# CarGeoLogger.net
KiCad netlist of a schematic drawn in Altium Designer
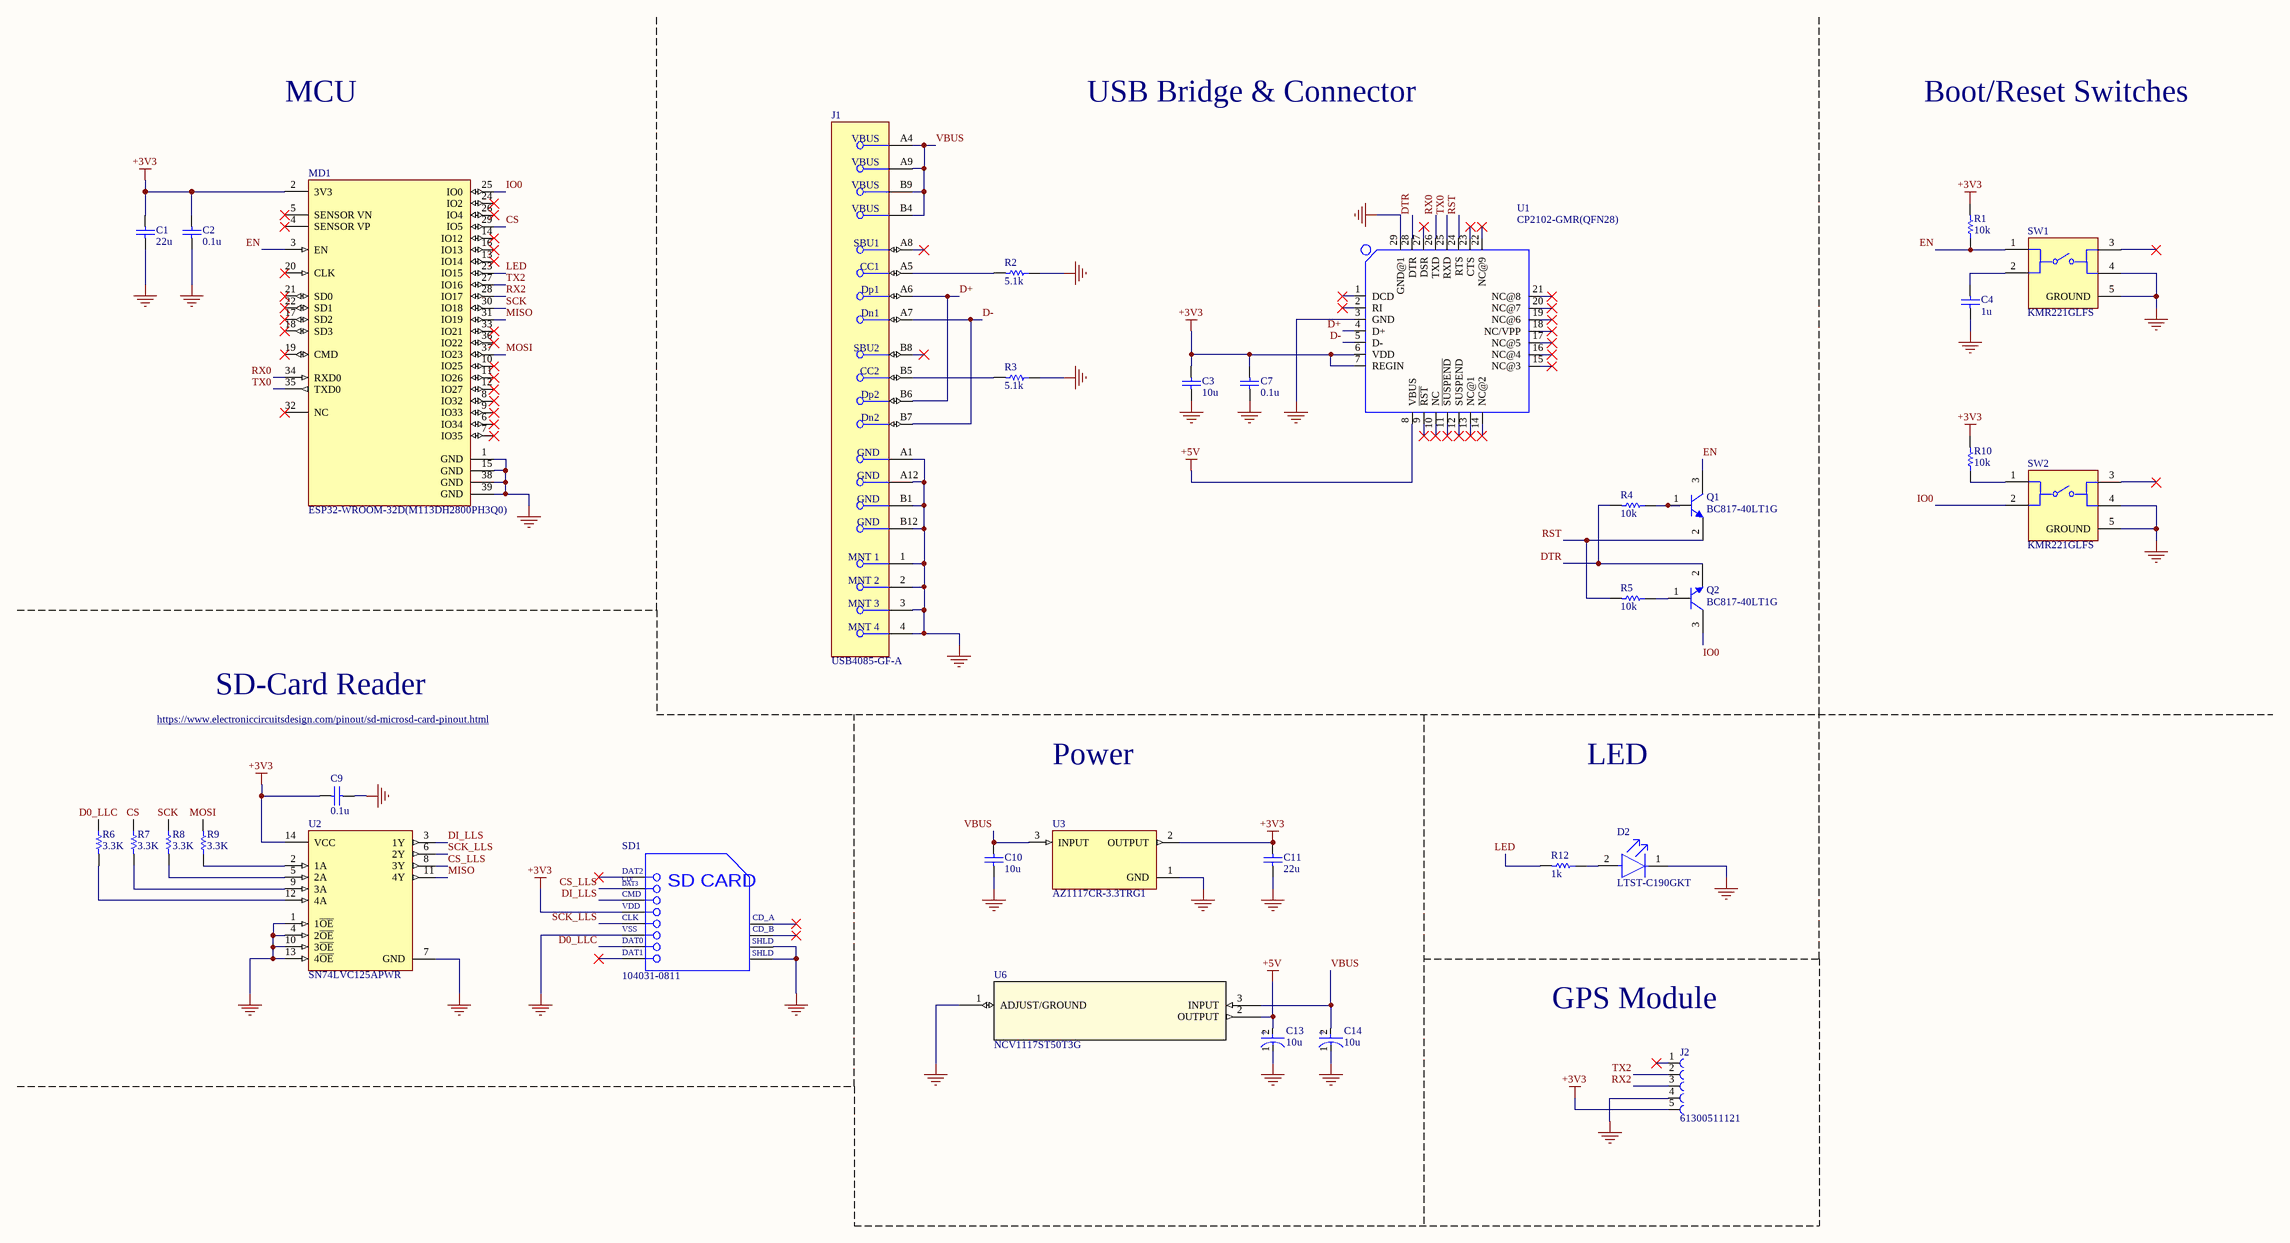
[diagram p0: CarGeoLogger.SchDoc]

(export (version "E")
  (design (tool "Eeschema 10.0.6"))
  (components
    (comp (ref "C1")
      (value "22u")
      (footprint "CAPC1608X90X35ML10T15")
      (description "Chip Capacitor, 0603 (1608 Metric), F381A106MMAAH1")
      (fields (field (name "MANUFACTURER") "Murata"))
      (libsource (lib "Altium Content Vault") (part "CAP-NP-2"))
    )
    (comp (ref "C2")
      (value "0.1u")
      (footprint "CAPC1608X90X35ML10T15")
      (description "Chip Capacitor, 0603 (1608 Metric)")
      (fields (field (name "MANUFACTURER") "Murata"))
      (libsource (lib "Altium Content Vault") (part "CAP-NP-2"))
    )
    (comp (ref "C3")
      (value "10u")
      (footprint "CAPC1608X90X35ML10T15")
      (description "Chip Capacitor, 0603 (1608 Metric)")
      (fields (field (name "MANUFACTURER") "Murata"))
      (libsource (lib "Altium Content Vault") (part "CAP-NP-2"))
    )
    (comp (ref "C4")
      (value "1u")
      (footprint "CAPC1608X90X35ML10T15")
      (description "Chip Capacitor, 0603 (1608 Metric)")
      (fields (field (name "MANUFACTURER") "Murata"))
      (libsource (lib "Altium Content Vault") (part "CAP-NP-2"))
    )
    (comp (ref "C7")
      (value "0.1u")
      (footprint "CAPC1608X90X35ML10T15")
      (description "Chip Capacitor, 0603 (1608 Metric)")
      (fields (field (name "MANUFACTURER") "Murata"))
      (libsource (lib "Altium Content Vault") (part "CAP-NP-2"))
    )
    (comp (ref "C9")
      (value "0.1u")
      (footprint "CAPC1608X90X35ML10T15")
      (description "Chip Capacitor, 0603 (1608 Metric)")
      (fields (field (name "MANUFACTURER") "Murata"))
      (libsource (lib "Altium Content Vault") (part "CAP-NP-2"))
    )
    (comp (ref "C10")
      (value "10u")
      (footprint "CAPC1608X90X35ML10T15")
      (description "Chip Capacitor, 0603 (1608 Metric)")
      (fields (field (name "MANUFACTURER") "Murata"))
      (libsource (lib "Altium Content Vault") (part "CAP-NP-2"))
    )
    (comp (ref "C11")
      (value "22u")
      (footprint "CAPC1608X90X35ML10T15")
      (description "Chip Capacitor, 0603 (1608 Metric), F381A106MMAAH1")
      (fields (field (name "MANUFACTURER") "Murata"))
      (libsource (lib "Altium Content Vault") (part "CAP-NP-2"))
    )
    (comp (ref "C13")
      (value "10u")
      (footprint "FP-F38M-MFG")
      (description "CAP TANT POLY 10UF 10V SMD")
      (fields
        (field (name "MANUFACTURER PART NUMBER") "F381A106MMAAH1")
        (field (name "OCTOPART") "https://octopart.com/f381a106mmaah1-avx-67040376")
      )
      (libsource (lib "Altium Content Vault") (part "cf48714ba7e38822c1575c7ec0b6d1f"))
    )
    (comp (ref "C14")
      (value "10u")
      (footprint "FP-F38M-MFG")
      (description "CAP TANT POLY 10UF 10V SMD")
      (fields
        (field (name "MANUFACTURER PART NUMBER") "F381A106MMAAH1")
        (field (name "OCTOPART") "https://octopart.com/f381a106mmaah1-avx-67040376")
      )
      (libsource (lib "Altium Content Vault") (part "cf48714ba7e38822c1575c7ec0b6d1f"))
    )
    (comp (ref "D2")
      (value "LTST-C190GKT")
      (footprint "FP-LTST-C190GKT-MFG")
      (description "LED GREEN CLEAR CHIP SMD")
      (fields (field (name "VOLTAGE") "2V"))
      (libsource (lib "Altium Content Vault") (part "8706943c75ba83719d021d2fdc84c58"))
    )
    (comp (ref "J1")
      (value "USB4085-GF-A")
      (footprint "FP-USB4085-GF-A-MFG")
      (description "CONN RCPT USB2.0 TYPE C 24POS RA")
      (libsource (lib "Altium Content Vault") (part "10fa745527c8b974685cbca3c197132"))
    )
    (comp (ref "J2")
      (value "61300511121")
      (footprint "61300511121")
      (description "Connector Header Through Hole 5 position 0.100 (2.54mm)")
      (fields (field (name "MF") "Wurth Electronics"))
      (libsource (lib "Kendrick Nguyen") (part "61300511121"))
    )
    (comp (ref "MD1")
      (value "ESP32-WROOM-32D(M113DH2800PH3Q0)")
      (footprint "FP-ESP32-WROOM-32D_M113DH-MFG")
      (description "RX TXRX MOD WIFI TRACE ANT SMD")
      (libsource (lib "Altium Content Vault") (part "68cda691c5ebc01e0f685e2e9d3fb9b"))
    )
    (comp (ref "Q1")
      (value "BC817-40LT1G")
      (footprint "ONSC-SOT-23-3-318-08_V")
      (description "General Purpose Transistor, NPN Silicon, 3-Pin SOT-23, Pb-Free, Tape and Reel")
      (fields (field (name "MANUFACTURER") "On Semiconductor"))
      (libsource (lib "Altium Content Vault") (part "ONSC-NPN-B1E2C3-3"))
    )
    (comp (ref "Q2")
      (value "BC817-40LT1G")
      (footprint "ONSC-SOT-23-3-318-08_V")
      (description "General Purpose Transistor, NPN Silicon, 3-Pin SOT-23, Pb-Free, Tape and Reel")
      (fields (field (name "MANUFACTURER") "On Semiconductor"))
      (libsource (lib "Altium Content Vault") (part "ONSC-NPN-B1E2C3-3"))
    )
    (comp (ref "R1")
      (value "10k")
      (footprint "RESC1609X50X30NL8T20")
      (description "Chip Resistor, 0603 (1608 Metric)")
      (fields (field (name "MANUFACTURER") "Vishay Semiconductor"))
      (libsource (lib "Altium Content Vault") (part "RES-2"))
    )
    (comp (ref "R2")
      (value "5.1k")
      (footprint "RESC1609X50X30NL8T20")
      (description "Chip Resistor, 0603 (1608 Metric)")
      (fields (field (name "MANUFACTURER") "Vishay Semiconductor"))
      (libsource (lib "Altium Content Vault") (part "RES-2"))
    )
    (comp (ref "R3")
      (value "5.1k")
      (footprint "RESC1609X50X30NL8T20")
      (description "Chip Resistor, 0603 (1608 Metric)")
      (fields (field (name "MANUFACTURER") "Vishay Semiconductor"))
      (libsource (lib "Altium Content Vault") (part "RES-2"))
    )
    (comp (ref "R4")
      (value "10k")
      (footprint "RESC1609X50X30NL8T20")
      (description "Chip Resistor, 0603 (1608 Metric)")
      (fields (field (name "MANUFACTURER") "Vishay Semiconductor"))
      (libsource (lib "Altium Content Vault") (part "RES-2"))
    )
    (comp (ref "R5")
      (value "10k")
      (footprint "RESC1609X50X30NL8T20")
      (description "Chip Resistor, 0603 (1608 Metric)")
      (fields (field (name "MANUFACTURER") "Vishay Semiconductor"))
      (libsource (lib "Altium Content Vault") (part "RES-2"))
    )
    (comp (ref "R6")
      (value "3.3K")
      (footprint "RESC1609X50X30NL8T20")
      (description "Chip Resistor, 0603 (1608 Metric)")
      (fields (field (name "MANUFACTURER") "Vishay Semiconductor"))
      (libsource (lib "Altium Content Vault") (part "RES-2"))
    )
    (comp (ref "R7")
      (value "3.3K")
      (footprint "RESC1609X50X30NL8T20")
      (description "Chip Resistor, 0603 (1608 Metric)")
      (fields (field (name "MANUFACTURER") "Vishay Semiconductor"))
      (libsource (lib "Altium Content Vault") (part "RES-2"))
    )
    (comp (ref "R8")
      (value "3.3K")
      (footprint "RESC1609X50X30NL8T20")
      (description "Chip Resistor, 0603 (1608 Metric)")
      (fields (field (name "MANUFACTURER") "Vishay Semiconductor"))
      (libsource (lib "Altium Content Vault") (part "RES-2"))
    )
    (comp (ref "R9")
      (value "3.3K")
      (footprint "RESC1609X50X30NL8T20")
      (description "Chip Resistor, 0603 (1608 Metric)")
      (fields (field (name "MANUFACTURER") "Vishay Semiconductor"))
      (libsource (lib "Altium Content Vault") (part "RES-2"))
    )
    (comp (ref "R10")
      (value "10k")
      (footprint "RESC1609X50X30NL8T20")
      (description "Chip Resistor, 0603 (1608 Metric)")
      (fields (field (name "MANUFACTURER") "Vishay Semiconductor"))
      (libsource (lib "Altium Content Vault") (part "RES-2"))
    )
    (comp (ref "R12")
      (value "1k")
      (footprint "RESC1609X50X30NL8T20")
      (description "Chip Resistor, 0603 (1608 Metric)")
      (fields (field (name "MANUFACTURER") "Vishay Semiconductor"))
      (libsource (lib "Altium Content Vault") (part "RES-2"))
    )
    (comp (ref "SD1")
      (value "104031-0811")
      (footprint "MOLX-104031-0811_V")
      (description "Micro SD Card, RA, -25 to 85 degC, 8-Pin SMD, RoHS, Tape and Reel")
      (fields (field (name "MANUFACTURER") "Molex"))
      (libsource (lib "Altium Content Vault") (part "CN-SD-8-2SW-2S"))
    )
    (comp (ref "SW1")
      (value "KMR221GLFS")
      (footprint "FP-KMR221GLFS-MFG")
      (description "SWITCH TACTILE SPST-NO 0.05A 32V")
      (libsource (lib "Altium Content Vault") (part "067e1cfe0b8977aedbfee7786663f4c"))
    )
    (comp (ref "SW2")
      (value "KMR221GLFS")
      (footprint "FP-KMR221GLFS-MFG")
      (description "SWITCH TACTILE SPST-NO 0.05A 32V")
      (libsource (lib "Altium Content Vault") (part "067e1cfe0b8977aedbfee7786663f4c"))
    )
    (comp (ref "U1")
      (value "CP2102-GMR(QFN28)")
      (footprint "QFN28G_0.5-5X5MM")
      (description "USB Bridge, USB to UART USB 2.0 UART Interface 28-QFN _5x5_")
      (fields (field (name "MP") "CP2102-GMR") (field (name "MF") "Silicon"))
      (libsource (lib "Kendrick Nguyen") (part "INTERFACE-CP2102-GMR(QFN28)"))
    )
    (comp (ref "U2")
      (value "SN74LVC125APWR")
      (footprint "FP-PW0014A-IPC_B")
      (description "IC BUF NON-INVERT 3.6V 14TSSOP")
      (libsource (lib "Altium Content Vault") (part "0c185306b27c65c3e4a0d950f37c68a"))
    )
    (comp (ref "U3")
      (value "AZ1117CR-3.3TRG1")
      (footprint "FP-SOT89-MFG")
      (description "IC REG LINEAR 3.3V 800MA SOT89")
      (fields
        (field (name "OCTOPART") "https://octopart.com/az1117cr-3.3trg1-diodes+inc.-30954805")
        (field (name "MANUFACTURER") "Diodes Inc.")
      )
      (libsource (lib "Altium Content Vault") (part "80dc4d5e0c5bf011f486f511683fde3"))
    )
    (comp (ref "U6")
      (value "NCV1117ST50T3G")
      (footprint "SOT223-3_ONS")
      (description "No Description Available")
      (fields (field (name "COPYRIGHT") "Copyright (C) 2022 Ultra Librarian. All rights reserved."))
      (libsource (lib "Kendrick Nguyen") (part "NCV1117ST50T3G"))
    )
  )
  (nets
    (net (code "1") (name "+3V3") (class "Default")
      (node (ref "C1") (pin "2") (pinfunction "2_2") (pintype "passive"))
      (node (ref "C11") (pin "2") (pinfunction "2_2") (pintype "passive"))
      (node (ref "C2") (pin "2") (pinfunction "2_2") (pintype "passive"))
      (node (ref "C3") (pin "2") (pinfunction "2_2") (pintype "passive"))
      (node (ref "C7") (pin "2") (pinfunction "2_2") (pintype "passive"))
      (node (ref "C9") (pin "2") (pinfunction "2_2") (pintype "passive"))
      (node (ref "J2") (pin "5") (pinfunction "5_5") (pintype "passive"))
      (node (ref "MD1") (pin "2") (pinfunction "3V3_2") (pintype "power_in"))
      (node (ref "R1") (pin "2") (pinfunction "2_2") (pintype "passive"))
      (node (ref "R10") (pin "2") (pinfunction "2_2") (pintype "passive"))
      (node (ref "SD1") (pin "4") (pinfunction "VDD_4") (pintype "passive"))
      (node (ref "U1") (pin "6") (pinfunction "VDD_6") (pintype "bidirectional"))
      (node (ref "U1") (pin "7") (pinfunction "REGIN_7") (pintype "bidirectional"))
      (node (ref "U2") (pin "14") (pinfunction "VCC_14") (pintype "power_in"))
      (node (ref "U3") (pin "2") (pinfunction "OUTPUT_2") (pintype "output"))
    )
    (net (code "2") (name "+5V") (class "Default")
      (node (ref "C13") (pin "2") (pinfunction "A_2") (pintype "passive"))
      (node (ref "U1") (pin "8") (pinfunction "VBUS_8") (pintype "bidirectional"))
      (node (ref "U6") (pin "2") (pinfunction "OUTPUT_2") (pintype "output"))
    )
    (net (code "3") (name "/CS") (class "Default")
      (node (ref "MD1") (pin "29") (pinfunction "IO5_29") (pintype "bidirectional"))
      (node (ref "R7") (pin "1") (pinfunction "1_1") (pintype "passive"))
    )
    (net (code "4") (name "/CS_LLS") (class "Default")
      (node (ref "SD1") (pin "2") (pinfunction "CMD_2") (pintype "passive"))
      (node (ref "U2") (pin "8") (pinfunction "3Y_8") (pintype "output"))
    )
    (net (code "5") (name "/D+") (class "Default")
      (node (ref "J1") (pin "A6") (pinfunction "Dp1_A6") (pintype "bidirectional"))
      (node (ref "J1") (pin "B6") (pinfunction "Dp2_B6") (pintype "bidirectional"))
      (node (ref "U1") (pin "4") (pinfunction "D+_4") (pintype "bidirectional"))
    )
    (net (code "6") (name "/D-") (class "Default")
      (node (ref "J1") (pin "A7") (pinfunction "Dn1_A7") (pintype "bidirectional"))
      (node (ref "J1") (pin "B7") (pinfunction "Dn2_B7") (pintype "bidirectional"))
      (node (ref "U1") (pin "5") (pinfunction "D-_5") (pintype "bidirectional"))
    )
    (net (code "7") (name "/D0_LLC") (class "Default")
      (node (ref "R6") (pin "1") (pinfunction "1_1") (pintype "passive"))
      (node (ref "SD1") (pin "7") (pinfunction "DAT0_7") (pintype "passive"))
    )
    (net (code "8") (name "/DI_LLS") (class "Default")
      (node (ref "SD1") (pin "3") (pinfunction "VSS1_3") (pintype "passive"))
      (node (ref "U2") (pin "3") (pinfunction "1Y_3") (pintype "output"))
    )
    (net (code "9") (name "/DTR") (class "Default")
      (node (ref "Q2") (pin "2") (pinfunction "E_2") (pintype "passive"))
      (node (ref "R4") (pin "2") (pinfunction "2_2") (pintype "passive"))
      (node (ref "U1") (pin "28") (pinfunction "DTR_28") (pintype "bidirectional"))
    )
    (net (code "10") (name "/EN") (class "Default")
      (node (ref "MD1") (pin "3") (pinfunction "EN_3") (pintype "input"))
      (node (ref "Q1") (pin "3") (pinfunction "C_3") (pintype "passive"))
      (node (ref "R1") (pin "1") (pinfunction "1_1") (pintype "passive"))
      (node (ref "SW1") (pin "1") (pinfunction "1_1") (pintype "passive"))
    )
    (net (code "11") (name "/IO0") (class "Default")
      (node (ref "MD1") (pin "25") (pinfunction "IO0_25") (pintype "bidirectional"))
      (node (ref "Q2") (pin "3") (pinfunction "C_3") (pintype "passive"))
      (node (ref "SW2") (pin "2") (pinfunction "2_2") (pintype "passive"))
    )
    (net (code "12") (name "/LED") (class "Default")
      (node (ref "MD1") (pin "23") (pinfunction "IO15_23") (pintype "bidirectional"))
      (node (ref "R12") (pin "2") (pinfunction "2_2") (pintype "passive"))
    )
    (net (code "13") (name "/MISO") (class "Default")
      (node (ref "MD1") (pin "31") (pinfunction "IO19_31") (pintype "bidirectional"))
      (node (ref "U2") (pin "11") (pinfunction "4Y_11") (pintype "output"))
    )
    (net (code "14") (name "/MOSI") (class "Default")
      (node (ref "MD1") (pin "37") (pinfunction "IO23_37") (pintype "bidirectional"))
      (node (ref "R9") (pin "2") (pinfunction "2_2") (pintype "passive"))
    )
    (net (code "15") (name "/RST") (class "Default")
      (node (ref "Q1") (pin "2") (pinfunction "E_2") (pintype "passive"))
      (node (ref "R5") (pin "2") (pinfunction "2_2") (pintype "passive"))
      (node (ref "U1") (pin "24") (pinfunction "RTS_24") (pintype "bidirectional"))
    )
    (net (code "16") (name "/RX0") (class "Default")
      (node (ref "MD1") (pin "34") (pinfunction "RXD0_34") (pintype "input"))
      (node (ref "U1") (pin "26") (pinfunction "TXD_26") (pintype "bidirectional"))
    )
    (net (code "17") (name "/RX2") (class "Default")
      (node (ref "J2") (pin "3") (pinfunction "3_3") (pintype "passive"))
      (node (ref "MD1") (pin "28") (pinfunction "IO17_28") (pintype "bidirectional"))
    )
    (net (code "18") (name "/SCK") (class "Default")
      (node (ref "MD1") (pin "30") (pinfunction "IO18_30") (pintype "bidirectional"))
      (node (ref "R8") (pin "1") (pinfunction "1_1") (pintype "passive"))
    )
    (net (code "19") (name "/SCK_LLS") (class "Default")
      (node (ref "SD1") (pin "5") (pinfunction "CLK_5") (pintype "passive"))
      (node (ref "U2") (pin "6") (pinfunction "2Y_6") (pintype "output"))
    )
    (net (code "20") (name "/TX0") (class "Default")
      (node (ref "MD1") (pin "35") (pinfunction "TXD0_35") (pintype "output"))
      (node (ref "U1") (pin "25") (pinfunction "RXD_25") (pintype "bidirectional"))
    )
    (net (code "21") (name "/TX2") (class "Default")
      (node (ref "J2") (pin "2") (pinfunction "2_2") (pintype "passive"))
      (node (ref "MD1") (pin "27") (pinfunction "IO16_27") (pintype "bidirectional"))
    )
    (net (code "22") (name "/VBUS") (class "Default")
      (node (ref "C10") (pin "2") (pinfunction "2_2") (pintype "passive"))
      (node (ref "C14") (pin "2") (pinfunction "A_2") (pintype "passive"))
      (node (ref "J1") (pin "A4") (pinfunction "VBUS_A4") (pintype "power_in"))
      (node (ref "J1") (pin "A9") (pinfunction "VBUS_A9") (pintype "power_in"))
      (node (ref "J1") (pin "B4") (pinfunction "VBUS_B4") (pintype "power_in"))
      (node (ref "J1") (pin "B9") (pinfunction "VBUS_B9") (pintype "power_in"))
      (node (ref "U3") (pin "3") (pinfunction "INPUT_3") (pintype "input"))
      (node (ref "U6") (pin "3") (pinfunction "INPUT_3") (pintype "input"))
    )
    (net (code "23") (name "<NO NET>") (class "Default")
      (node (ref "C1") (pin "1") (pinfunction "1_1") (pintype "passive"))
      (node (ref "C10") (pin "1") (pinfunction "1_1") (pintype "passive"))
      (node (ref "C11") (pin "1") (pinfunction "1_1") (pintype "passive"))
      (node (ref "C13") (pin "1") (pinfunction "C_1") (pintype "passive"))
      (node (ref "C14") (pin "1") (pinfunction "C_1") (pintype "passive"))
      (node (ref "C2") (pin "1") (pinfunction "1_1") (pintype "passive"))
      (node (ref "C3") (pin "1") (pinfunction "1_1") (pintype "passive"))
      (node (ref "C4") (pin "1") (pinfunction "1_1") (pintype "passive"))
      (node (ref "C7") (pin "1") (pinfunction "1_1") (pintype "passive"))
      (node (ref "C9") (pin "1") (pinfunction "1_1") (pintype "passive"))
      (node (ref "D2") (pin "1") (pinfunction "C_1") (pintype "passive"))
      (node (ref "J1") (pin "1") (pinfunction "MNT_1_1") (pintype "passive"))
      (node (ref "J1") (pin "2") (pinfunction "MNT_2_2") (pintype "passive"))
      (node (ref "J1") (pin "3") (pinfunction "MNT_3_3") (pintype "passive"))
      (node (ref "J1") (pin "4") (pinfunction "MNT_4_4") (pintype "passive"))
      (node (ref "J1") (pin "A1") (pinfunction "GND_A1") (pintype "power_in"))
      (node (ref "J1") (pin "A12") (pinfunction "GND_A12") (pintype "power_in"))
      (node (ref "J1") (pin "B1") (pinfunction "GND_B1") (pintype "power_in"))
      (node (ref "J1") (pin "B12") (pinfunction "GND_B12") (pintype "power_in"))
      (node (ref "J2") (pin "4") (pinfunction "4_4") (pintype "passive"))
      (node (ref "MD1") (pin "1") (pinfunction "GND_1") (pintype "power_in"))
      (node (ref "MD1") (pin "15") (pinfunction "GND_15") (pintype "power_in"))
      (node (ref "MD1") (pin "38") (pinfunction "GND_38") (pintype "power_in"))
      (node (ref "MD1") (pin "39") (pinfunction "GND_39") (pintype "power_in"))
      (node (ref "R2") (pin "1") (pinfunction "1_1") (pintype "passive"))
      (node (ref "R3") (pin "1") (pinfunction "1_1") (pintype "passive"))
      (node (ref "SD1") (pin "11") (pinfunction "SHLD1_11") (pintype "passive"))
      (node (ref "SD1") (pin "12") (pinfunction "SHLD2_12") (pintype "passive"))
      (node (ref "SD1") (pin "6") (pinfunction "VSS2_6") (pintype "passive"))
      (node (ref "SW1") (pin "4") (pinfunction "4_4") (pintype "passive"))
      (node (ref "SW1") (pin "5") (pinfunction "GROUND_5") (pintype "power_in"))
      (node (ref "SW2") (pin "4") (pinfunction "4_4") (pintype "passive"))
      (node (ref "SW2") (pin "5") (pinfunction "GROUND_5") (pintype "power_in"))
      (node (ref "U1") (pin "29") (pinfunction "GND@1_29") (pintype "bidirectional"))
      (node (ref "U1") (pin "3") (pinfunction "GND_3") (pintype "bidirectional"))
      (node (ref "U2") (pin "1") (pinfunction "1~{OE}_1") (pintype "input"))
      (node (ref "U2") (pin "10") (pinfunction "3~{OE}_10") (pintype "input"))
      (node (ref "U2") (pin "13") (pinfunction "4~{OE}_13") (pintype "input"))
      (node (ref "U2") (pin "4") (pinfunction "2~{OE}_4") (pintype "input"))
      (node (ref "U2") (pin "7") (pinfunction "GND_7") (pintype "power_in"))
      (node (ref "U3") (pin "1") (pinfunction "GND_1") (pintype "power_in"))
      (node (ref "U6") (pin "1") (pinfunction "ADJUST/GROUND_1") (pintype "bidirectional"))
    )
    (net (code "24") (name "Net-(C4-Pad2)") (class "Default")
      (node (ref "C4") (pin "2") (pinfunction "2_2") (pintype "passive"))
      (node (ref "SW1") (pin "2") (pinfunction "2_2") (pintype "passive"))
    )
    (net (code "25") (name "Net-(D2-A)") (class "Default")
      (node (ref "D2") (pin "2") (pinfunction "A_2") (pintype "passive"))
      (node (ref "R12") (pin "1") (pinfunction "1_1") (pintype "passive"))
    )
    (net (code "26") (name "Net-(J1-CC1)") (class "Default")
      (node (ref "J1") (pin "A5") (pinfunction "CC1_A5") (pintype "bidirectional"))
      (node (ref "R2") (pin "2") (pinfunction "2_2") (pintype "passive"))
    )
    (net (code "27") (name "Net-(J1-CC2)") (class "Default")
      (node (ref "J1") (pin "B5") (pinfunction "CC2_B5") (pintype "bidirectional"))
      (node (ref "R3") (pin "2") (pinfunction "2_2") (pintype "passive"))
    )
    (net (code "28") (name "Net-(Q1-B)") (class "Default")
      (node (ref "Q1") (pin "1") (pinfunction "B_1") (pintype "passive"))
      (node (ref "R4") (pin "1") (pinfunction "1_1") (pintype "passive"))
    )
    (net (code "29") (name "Net-(Q2-B)") (class "Default")
      (node (ref "Q2") (pin "1") (pinfunction "B_1") (pintype "passive"))
      (node (ref "R5") (pin "1") (pinfunction "1_1") (pintype "passive"))
    )
    (net (code "30") (name "Net-(R10-Pad1)") (class "Default")
      (node (ref "R10") (pin "1") (pinfunction "1_1") (pintype "passive"))
      (node (ref "SW2") (pin "1") (pinfunction "1_1") (pintype "passive"))
    )
    (net (code "31") (name "Net-(U2-1A)") (class "Default")
      (node (ref "R9") (pin "1") (pinfunction "1_1") (pintype "passive"))
      (node (ref "U2") (pin "2") (pinfunction "1A_2") (pintype "input"))
    )
    (net (code "32") (name "Net-(U2-2A)") (class "Default")
      (node (ref "R8") (pin "2") (pinfunction "2_2") (pintype "passive"))
      (node (ref "U2") (pin "5") (pinfunction "2A_5") (pintype "input"))
    )
    (net (code "33") (name "Net-(U2-3A)") (class "Default")
      (node (ref "R7") (pin "2") (pinfunction "2_2") (pintype "passive"))
      (node (ref "U2") (pin "9") (pinfunction "3A_9") (pintype "input"))
    )
    (net (code "34") (name "Net-(U2-4A)") (class "Default")
      (node (ref "R6") (pin "2") (pinfunction "2_2") (pintype "passive"))
      (node (ref "U2") (pin "12") (pinfunction "4A_12") (pintype "input"))
    )
    (net (code "35") (name "unconnected-(J1-SBU1-PadA8)") (class "Default")
      (node (ref "J1") (pin "A8") (pinfunction "SBU1_A8") (pintype "bidirectional+no_connect"))
    )
    (net (code "36") (name "unconnected-(J1-SBU2-PadB8)") (class "Default")
      (node (ref "J1") (pin "B8") (pinfunction "SBU2_B8") (pintype "bidirectional+no_connect"))
    )
    (net (code "37") (name "unconnected-(J2-Pad1)") (class "Default")
      (node (ref "J2") (pin "1") (pinfunction "1_1") (pintype "passive+no_connect"))
    )
    (net (code "38") (name "unconnected-(MD1-CLK-Pad20)") (class "Default")
      (node (ref "MD1") (pin "20") (pinfunction "CLK_20") (pintype "input+no_connect"))
    )
    (net (code "39") (name "unconnected-(MD1-CMD-Pad19)") (class "Default")
      (node (ref "MD1") (pin "19") (pinfunction "CMD_19") (pintype "bidirectional+no_connect"))
    )
    (net (code "40") (name "unconnected-(MD1-IO2-Pad24)") (class "Default")
      (node (ref "MD1") (pin "24") (pinfunction "IO2_24") (pintype "bidirectional+no_connect"))
    )
    (net (code "41") (name "unconnected-(MD1-IO4-Pad26)") (class "Default")
      (node (ref "MD1") (pin "26") (pinfunction "IO4_26") (pintype "bidirectional+no_connect"))
    )
    (net (code "42") (name "unconnected-(MD1-IO12-Pad14)") (class "Default")
      (node (ref "MD1") (pin "14") (pinfunction "IO12_14") (pintype "bidirectional+no_connect"))
    )
    (net (code "43") (name "unconnected-(MD1-IO13-Pad16)") (class "Default")
      (node (ref "MD1") (pin "16") (pinfunction "IO13_16") (pintype "bidirectional+no_connect"))
    )
    (net (code "44") (name "unconnected-(MD1-IO14-Pad13)") (class "Default")
      (node (ref "MD1") (pin "13") (pinfunction "IO14_13") (pintype "bidirectional+no_connect"))
    )
    (net (code "45") (name "unconnected-(MD1-IO21-Pad33)") (class "Default")
      (node (ref "MD1") (pin "33") (pinfunction "IO21_33") (pintype "bidirectional+no_connect"))
    )
    (net (code "46") (name "unconnected-(MD1-IO22-Pad36)") (class "Default")
      (node (ref "MD1") (pin "36") (pinfunction "IO22_36") (pintype "bidirectional+no_connect"))
    )
    (net (code "47") (name "unconnected-(MD1-IO25-Pad10)") (class "Default")
      (node (ref "MD1") (pin "10") (pinfunction "IO25_10") (pintype "bidirectional+no_connect"))
    )
    (net (code "48") (name "unconnected-(MD1-IO26-Pad11)") (class "Default")
      (node (ref "MD1") (pin "11") (pinfunction "IO26_11") (pintype "bidirectional+no_connect"))
    )
    (net (code "49") (name "unconnected-(MD1-IO27-Pad12)") (class "Default")
      (node (ref "MD1") (pin "12") (pinfunction "IO27_12") (pintype "bidirectional+no_connect"))
    )
    (net (code "50") (name "unconnected-(MD1-IO32-Pad8)") (class "Default")
      (node (ref "MD1") (pin "8") (pinfunction "IO32_8") (pintype "bidirectional+no_connect"))
    )
    (net (code "51") (name "unconnected-(MD1-IO33-Pad9)") (class "Default")
      (node (ref "MD1") (pin "9") (pinfunction "IO33_9") (pintype "bidirectional+no_connect"))
    )
    (net (code "52") (name "unconnected-(MD1-IO34-Pad6)") (class "Default")
      (node (ref "MD1") (pin "6") (pinfunction "IO34_6") (pintype "bidirectional+no_connect"))
    )
    (net (code "53") (name "unconnected-(MD1-IO35-Pad7)") (class "Default")
      (node (ref "MD1") (pin "7") (pinfunction "IO35_7") (pintype "bidirectional+no_connect"))
    )
    (net (code "54") (name "unconnected-(MD1-NC-Pad32)") (class "Default")
      (node (ref "MD1") (pin "32") (pinfunction "NC_32") (pintype "passive+no_connect"))
    )
    (net (code "55") (name "unconnected-(MD1-SD0-Pad21)") (class "Default")
      (node (ref "MD1") (pin "21") (pinfunction "SD0_21") (pintype "bidirectional+no_connect"))
    )
    (net (code "56") (name "unconnected-(MD1-SD1-Pad22)") (class "Default")
      (node (ref "MD1") (pin "22") (pinfunction "SD1_22") (pintype "bidirectional+no_connect"))
    )
    (net (code "57") (name "unconnected-(MD1-SD2-Pad17)") (class "Default")
      (node (ref "MD1") (pin "17") (pinfunction "SD2_17") (pintype "bidirectional+no_connect"))
    )
    (net (code "58") (name "unconnected-(MD1-SD3-Pad18)") (class "Default")
      (node (ref "MD1") (pin "18") (pinfunction "SD3_18") (pintype "bidirectional+no_connect"))
    )
    (net (code "59") (name "unconnected-(MD1-SENSOR_VN-Pad5)") (class "Default")
      (node (ref "MD1") (pin "5") (pinfunction "SENSOR_VN_5") (pintype "passive+no_connect"))
    )
    (net (code "60") (name "unconnected-(MD1-SENSOR_VP-Pad4)") (class "Default")
      (node (ref "MD1") (pin "4") (pinfunction "SENSOR_VP_4") (pintype "passive+no_connect"))
    )
    (net (code "61") (name "unconnected-(SD1-CD_A-Pad9)") (class "Default")
      (node (ref "SD1") (pin "9") (pinfunction "CD_A_9") (pintype "passive+no_connect"))
    )
    (net (code "62") (name "unconnected-(SD1-CD_B-Pad10)") (class "Default")
      (node (ref "SD1") (pin "10") (pinfunction "CD_B_10") (pintype "passive+no_connect"))
    )
    (net (code "63") (name "unconnected-(SD1-CD{slash}DAT3-Pad1)") (class "Default")
      (node (ref "SD1") (pin "1") (pinfunction "CD/DAT3_1") (pintype "passive+no_connect"))
    )
    (net (code "64") (name "unconnected-(SD1-DAT1-Pad8)") (class "Default")
      (node (ref "SD1") (pin "8") (pinfunction "DAT1_8") (pintype "passive+no_connect"))
    )
    (net (code "65") (name "unconnected-(SW1-Pad3)") (class "Default")
      (node (ref "SW1") (pin "3") (pinfunction "3_3") (pintype "passive+no_connect"))
    )
    (net (code "66") (name "unconnected-(SW2-Pad3)") (class "Default")
      (node (ref "SW2") (pin "3") (pinfunction "3_3") (pintype "passive+no_connect"))
    )
    (net (code "67") (name "unconnected-(U1-CTS-Pad23)") (class "Default")
      (node (ref "U1") (pin "23") (pinfunction "CTS_23") (pintype "bidirectional+no_connect"))
    )
    (net (code "68") (name "unconnected-(U1-DCD-Pad1)") (class "Default")
      (node (ref "U1") (pin "1") (pinfunction "DCD_1") (pintype "bidirectional+no_connect"))
    )
    (net (code "69") (name "unconnected-(U1-DSR-Pad27)") (class "Default")
      (node (ref "U1") (pin "27") (pinfunction "DSR_27") (pintype "bidirectional+no_connect"))
    )
    (net (code "70") (name "unconnected-(U1-NC-Pad10)") (class "Default")
      (node (ref "U1") (pin "10") (pinfunction "NC_10") (pintype "bidirectional+no_connect"))
    )
    (net (code "71") (name "unconnected-(U1-NC@1-Pad13)") (class "Default")
      (node (ref "U1") (pin "13") (pinfunction "NC@1_13") (pintype "bidirectional+no_connect"))
    )
    (net (code "72") (name "unconnected-(U1-NC@2-Pad14)") (class "Default")
      (node (ref "U1") (pin "14") (pinfunction "NC@2_14") (pintype "bidirectional+no_connect"))
    )
    (net (code "73") (name "unconnected-(U1-NC@3-Pad15)") (class "Default")
      (node (ref "U1") (pin "15") (pinfunction "NC@3_15") (pintype "bidirectional+no_connect"))
    )
    (net (code "74") (name "unconnected-(U1-NC@4-Pad16)") (class "Default")
      (node (ref "U1") (pin "16") (pinfunction "NC@4_16") (pintype "bidirectional+no_connect"))
    )
    (net (code "75") (name "unconnected-(U1-NC@5-Pad17)") (class "Default")
      (node (ref "U1") (pin "17") (pinfunction "NC@5_17") (pintype "bidirectional+no_connect"))
    )
    (net (code "76") (name "unconnected-(U1-NC@6-Pad19)") (class "Default")
      (node (ref "U1") (pin "19") (pinfunction "NC@6_19") (pintype "bidirectional+no_connect"))
    )
    (net (code "77") (name "unconnected-(U1-NC@7-Pad20)") (class "Default")
      (node (ref "U1") (pin "20") (pinfunction "NC@7_20") (pintype "bidirectional+no_connect"))
    )
    (net (code "78") (name "unconnected-(U1-NC@8-Pad21)") (class "Default")
      (node (ref "U1") (pin "21") (pinfunction "NC@8_21") (pintype "bidirectional+no_connect"))
    )
    (net (code "79") (name "unconnected-(U1-NC@9-Pad22)") (class "Default")
      (node (ref "U1") (pin "22") (pinfunction "NC@9_22") (pintype "bidirectional+no_connect"))
    )
    (net (code "80") (name "unconnected-(U1-NC{slash}VPP-Pad18)") (class "Default")
      (node (ref "U1") (pin "18") (pinfunction "NC/VPP_18") (pintype "bidirectional+no_connect"))
    )
    (net (code "81") (name "unconnected-(U1-RI-Pad2)") (class "Default")
      (node (ref "U1") (pin "2") (pinfunction "RI_2") (pintype "bidirectional+no_connect"))
    )
    (net (code "82") (name "unconnected-(U1-SUSPEND-Pad12)") (class "Default")
      (node (ref "U1") (pin "12") (pinfunction "SUSPEND_12") (pintype "bidirectional+no_connect"))
    )
    (net (code "83") (name "unconnected-(U1-~{RST}-Pad9)") (class "Default")
      (node (ref "U1") (pin "9") (pinfunction "~{RST}_9") (pintype "bidirectional+no_connect"))
    )
    (net (code "84") (name "unconnected-(U1-~{SUSPEND}-Pad11)") (class "Default")
      (node (ref "U1") (pin "11") (pinfunction "~{SUSPEND}_11") (pintype "bidirectional+no_connect"))
    )
  )
)
